# seashell.net
KiCad netlist of a schematic drawn in Altium Designer
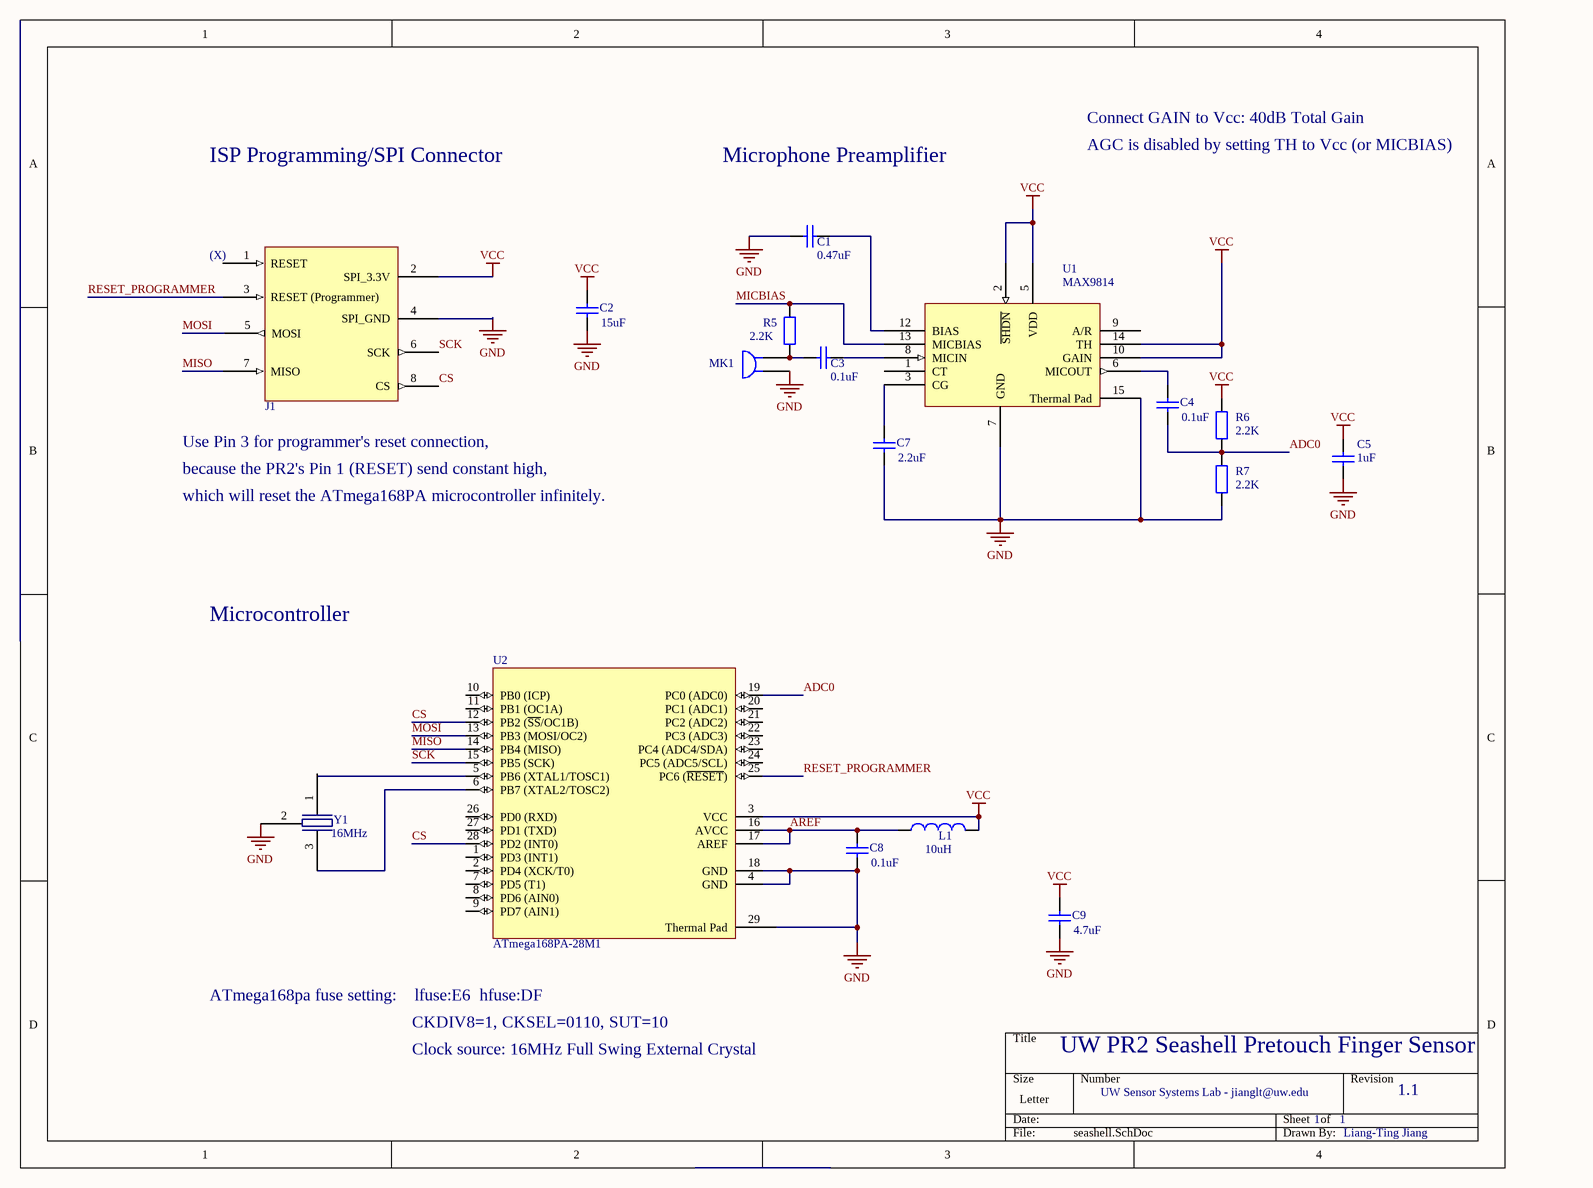
[diagram p0: seashell.SchDoc]

(export (version "E")
  (design (tool "Eeschema 10.0.6"))
  (components
    (comp (ref "C1")
      (value "0.47uF")
      (footprint "CAPC1608N")
      (description "0603 SMD Capacitor")
      (fields (field (name "PUBLISHER") "Altium Limited"))
      (libsource (lib "Miscellaneous Devices") (part "Cap"))
    )
    (comp (ref "C2")
      (value "15uF")
      (footprint "CAPC1608N")
      (description "0603 SMD Capacitor")
      (fields (field (name "PUBLISHER") "Altium Limited"))
      (libsource (lib "Miscellaneous Devices") (part "Cap"))
    )
    (comp (ref "C3")
      (value "0.1uF")
      (footprint "CAPC1608N")
      (description "0603 SMD Capacitor")
      (fields (field (name "PUBLISHER") "Altium Limited"))
      (libsource (lib "Miscellaneous Devices") (part "Cap"))
    )
    (comp (ref "C4")
      (value "0.1uF")
      (footprint "CAPC1608N")
      (description "0603 SMD Capacitor")
      (fields (field (name "PUBLISHER") "Altium Limited"))
      (libsource (lib "Miscellaneous Devices") (part "Cap"))
    )
    (comp (ref "C5")
      (value "1uF")
      (footprint "CAPC1608N")
      (description "0603 SMD Capacitor")
      (fields (field (name "PUBLISHER") "Altium Limited"))
      (libsource (lib "Miscellaneous Devices") (part "Cap"))
    )
    (comp (ref "C7")
      (value "2.2uF")
      (footprint "CAPC1608N")
      (description "0603 SMD Capacitor")
      (fields (field (name "PUBLISHER") "Altium Limited"))
      (libsource (lib "Miscellaneous Devices") (part "Cap"))
    )
    (comp (ref "C8")
      (value "0.1uF")
      (footprint "CAPC1608N")
      (description "0603 SMD Capacitor")
      (fields (field (name "PUBLISHER") "Altium Limited"))
      (libsource (lib "Miscellaneous Devices") (part "Cap"))
    )
    (comp (ref "C9")
      (value "4.7uF")
      (footprint "CAPC1608N")
      (description "0603 SMD Capacitor")
      (fields (field (name "PUBLISHER") "Altium Limited"))
      (libsource (lib "Miscellaneous Devices") (part "Cap"))
    )
    (comp (ref "J1")
      (value "FFC 8-PIN Connector (1mm)")
      (footprint "Hirose FFC connector 8-Pin")
      (description "FFC 8-PIN Connector (1mm) (SMT)")
      (libsource (lib "UW_PR2_FINERTIP_COMPONENTS") (part "FFC Connector-8Pin-SMT-1mm"))
    )
    (comp (ref "L1")
      (value "10uH")
      (footprint "INDC1608N")
      (description "0603 SMD Inductor")
      (fields (field (name "PUBLISHER") "Altium Limited"))
      (libsource (lib "Miscellaneous Devices") (part "Inductor"))
    )
    (comp (ref "MK1")
      (value "Panasonic WM-61A")
      (footprint "PIN2")
      (description "Electret Microphone")
      (fields (field (name "PUBLISHER") "Altium Limited"))
      (libsource (lib "Miscellaneous Devices") (part "Mic1"))
    )
    (comp (ref "R5")
      (value "2.2K")
      (footprint "RESC1608N")
      (description "0603 SMD Resistor")
      (fields (field (name "PUBLISHER") "Altium Limited"))
      (libsource (lib "Miscellaneous Devices") (part "Res2"))
    )
    (comp (ref "R6")
      (value "2.2K")
      (footprint "RESC1608N")
      (description "0603 SMD Resistor")
      (fields (field (name "PUBLISHER") "Altium Limited"))
      (libsource (lib "Miscellaneous Devices") (part "Res2"))
    )
    (comp (ref "R7")
      (value "2.2K")
      (footprint "RESC1608N")
      (description "0603 SMD Resistor")
      (fields (field (name "PUBLISHER") "Altium Limited"))
      (libsource (lib "Miscellaneous Devices") (part "Res2"))
    )
    (comp (ref "U1")
      (value "MAX9814")
      (footprint "QFN-14-Minnimum-Solder-Mask-Relief")
      (description "Microphone Amplifier with AGC and   Low-Noise Microphone Bias")
      (libsource (lib "UW_PR2_FINERTIP_COMPONENTS") (part "MAX9814"))
    )
    (comp (ref "U2")
      (value "ATmega168PA-28M1")
      (footprint "28M1")
      (description "8-Bit AVR Microcontroller with 8K Bytes of In-System Programmable Flash Memory")
      (fields (field (name "PUBLISHER") "Altium Limited"))
      (libsource (lib "UW_PR2_FINERTIP_COMPONENTS") (part "ATmega168-28M1"))
    )
    (comp (ref "Y1")
      (value "AVX PRQC16.00SR5010X000")
      (footprint "AVX-PRQC Ceramic Resomator SMD")
      (description "16MHz Ceramic Chip Resonator SMD")
      (fields (field (name "FREQUENCY") "16MHz"))
      (libsource (lib "UW_PR2_FINERTIP_COMPONENTS") (part "Ceramic Resonator SMT (w/ cap)"))
    )
  )
  (nets
    (net (code "1") (name "/ADC0") (class "Default")
      (node (ref "C4") (pin "1") (pinfunction "1_1") (pintype "passive"))
      (node (ref "R6") (pin "1") (pinfunction "1_1") (pintype "passive"))
      (node (ref "R7") (pin "2") (pinfunction "2_2") (pintype "passive"))
      (node (ref "U2") (pin "19") (pinfunction "PC0_(ADC0)_19") (pintype "bidirectional"))
    )
    (net (code "2") (name "/AREF") (class "Default")
      (node (ref "C8") (pin "2") (pinfunction "2_2") (pintype "passive"))
      (node (ref "L1") (pin "1") (pinfunction "1_1") (pintype "passive"))
      (node (ref "U2") (pin "16") (pinfunction "AVCC_16") (pintype "power_in"))
      (node (ref "U2") (pin "17") (pinfunction "AREF_17") (pintype "passive"))
    )
    (net (code "3") (name "/CS") (class "Default")
      (node (ref "J1") (pin "8") (pinfunction "CS_8") (pintype "output"))
      (node (ref "U2") (pin "12") (pinfunction "PB2_(~{SS}/OC1B)_12") (pintype "bidirectional"))
      (node (ref "U2") (pin "28") (pinfunction "PD2_(INT0)_28") (pintype "bidirectional"))
    )
    (net (code "4") (name "/MICBIAS") (class "Default")
      (node (ref "R5") (pin "2") (pinfunction "2_2") (pintype "passive"))
      (node (ref "U1") (pin "13") (pinfunction "MICBIAS_13") (pintype "power_in"))
    )
    (net (code "5") (name "/MISO") (class "Default")
      (node (ref "J1") (pin "7") (pinfunction "MISO_7") (pintype "input"))
      (node (ref "U2") (pin "14") (pinfunction "PB4_(MISO)_14") (pintype "bidirectional"))
    )
    (net (code "6") (name "/MOSI") (class "Default")
      (node (ref "J1") (pin "5") (pinfunction "MOSI_5") (pintype "output"))
      (node (ref "U2") (pin "13") (pinfunction "PB3_(MOSI/OC2)_13") (pintype "bidirectional"))
    )
    (net (code "7") (name "/RESET_PROGRAMMER") (class "Default")
      (node (ref "J1") (pin "3") (pinfunction "RESET_(Programmer)_3") (pintype "input"))
      (node (ref "U2") (pin "25") (pinfunction "PC6_(~{RESET})_25") (pintype "bidirectional"))
    )
    (net (code "8") (name "/SCK") (class "Default")
      (node (ref "J1") (pin "6") (pinfunction "SCK_6") (pintype "output"))
      (node (ref "U2") (pin "15") (pinfunction "PB5_(SCK)_15") (pintype "bidirectional"))
    )
    (net (code "9") (name "GND") (class "Default")
      (node (ref "C1") (pin "2") (pinfunction "2_2") (pintype "passive"))
      (node (ref "C2") (pin "2") (pinfunction "2_2") (pintype "passive"))
      (node (ref "C5") (pin "1") (pinfunction "1_1") (pintype "passive"))
      (node (ref "C7") (pin "2") (pinfunction "2_2") (pintype "passive"))
      (node (ref "C8") (pin "1") (pinfunction "1_1") (pintype "passive"))
      (node (ref "C9") (pin "2") (pinfunction "2_2") (pintype "passive"))
      (node (ref "J1") (pin "4") (pinfunction "SPI_GND_4") (pintype "power_in"))
      (node (ref "MK1") (pin "1") (pinfunction "1_1") (pintype "passive"))
      (node (ref "R7") (pin "1") (pinfunction "1_1") (pintype "passive"))
      (node (ref "U1") (pin "15") (pinfunction "Thermal_Pad_15") (pintype "passive"))
      (node (ref "U1") (pin "7") (pinfunction "GND_7") (pintype "power_in"))
      (node (ref "U2") (pin "18") (pinfunction "GND_18") (pintype "power_in"))
      (node (ref "U2") (pin "29") (pinfunction "Thermal_Pad_29") (pintype "power_in"))
      (node (ref "U2") (pin "4") (pinfunction "GND_4") (pintype "power_in"))
      (node (ref "Y1") (pin "2") (pinfunction "GND_2") (pintype "power_in"))
    )
    (net (code "10") (name "Net-(C3-Pad1)") (class "Default")
      (node (ref "C3") (pin "1") (pinfunction "1_1") (pintype "passive"))
      (node (ref "MK1") (pin "2") (pinfunction "2_2") (pintype "passive"))
      (node (ref "R5") (pin "1") (pinfunction "1_1") (pintype "passive"))
    )
    (net (code "11") (name "Net-(U1-BIAS)") (class "Default")
      (node (ref "C1") (pin "1") (pinfunction "1_1") (pintype "passive"))
      (node (ref "U1") (pin "12") (pinfunction "BIAS_12") (pintype "passive"))
    )
    (net (code "12") (name "Net-(U1-CG)") (class "Default")
      (node (ref "C7") (pin "1") (pinfunction "1_1") (pintype "passive"))
      (node (ref "U1") (pin "3") (pinfunction "CG_3") (pintype "passive"))
    )
    (net (code "13") (name "Net-(U1-MICIN)") (class "Default")
      (node (ref "C3") (pin "2") (pinfunction "2_2") (pintype "passive"))
      (node (ref "U1") (pin "8") (pinfunction "MICIN_8") (pintype "input"))
    )
    (net (code "14") (name "Net-(U1-MICOUT)") (class "Default")
      (node (ref "C4") (pin "2") (pinfunction "2_2") (pintype "passive"))
      (node (ref "U1") (pin "6") (pinfunction "MICOUT_6") (pintype "output"))
    )
    (net (code "15") (name "Net-(U2-PB6_(XTAL1{slash}TOSC1))") (class "Default")
      (node (ref "U2") (pin "5") (pinfunction "PB6_(XTAL1/TOSC1)_5") (pintype "bidirectional"))
      (node (ref "Y1") (pin "1") (pinfunction "IN/OUT_1") (pintype "passive"))
    )
    (net (code "16") (name "Net-(U2-PB7_(XTAL2{slash}TOSC2))") (class "Default")
      (node (ref "U2") (pin "6") (pinfunction "PB7_(XTAL2/TOSC2)_6") (pintype "bidirectional"))
      (node (ref "Y1") (pin "3") (pinfunction "OUT/IN_3") (pintype "passive"))
    )
    (net (code "17") (name "VCC") (class "Default")
      (node (ref "C2") (pin "1") (pinfunction "1_1") (pintype "passive"))
      (node (ref "C5") (pin "2") (pinfunction "2_2") (pintype "passive"))
      (node (ref "C9") (pin "1") (pinfunction "1_1") (pintype "passive"))
      (node (ref "J1") (pin "2") (pinfunction "SPI_3.3V_2") (pintype "power_in"))
      (node (ref "L1") (pin "2") (pinfunction "2_2") (pintype "passive"))
      (node (ref "R6") (pin "2") (pinfunction "2_2") (pintype "passive"))
      (node (ref "U1") (pin "10") (pinfunction "GAIN_10") (pintype "passive"))
      (node (ref "U1") (pin "14") (pinfunction "TH_14") (pintype "passive"))
      (node (ref "U1") (pin "2") (pinfunction "~{SHDN}_2") (pintype "input"))
      (node (ref "U1") (pin "5") (pinfunction "VDD_5") (pintype "power_in"))
      (node (ref "U2") (pin "3") (pinfunction "VCC_3") (pintype "power_in"))
    )
    (net (code "18") (name "unconnected-(J1-RESET-Pad1)") (class "Default")
      (node (ref "J1") (pin "1") (pinfunction "RESET_1") (pintype "input"))
    )
    (net (code "19") (name "unconnected-(U1-A{slash}R-Pad9)") (class "Default")
      (node (ref "U1") (pin "9") (pinfunction "A/R_9") (pintype "passive"))
    )
    (net (code "20") (name "unconnected-(U1-CT-Pad1)") (class "Default")
      (node (ref "U1") (pin "1") (pinfunction "CT_1") (pintype "passive"))
    )
    (net (code "21") (name "unconnected-(U1-NC-Pad4)") (class "Default")
      (node (ref "U1") (pin "4") (pinfunction "NC_4") (pintype "passive"))
    )
    (net (code "22") (name "unconnected-(U1-NC-Pad11)") (class "Default")
      (node (ref "U1") (pin "11") (pinfunction "NC_11") (pintype "passive"))
    )
    (net (code "23") (name "unconnected-(U2-PB0_(ICP)-Pad10)") (class "Default")
      (node (ref "U2") (pin "10") (pinfunction "PB0_(ICP)_10") (pintype "bidirectional"))
    )
    (net (code "24") (name "unconnected-(U2-PB1_(OC1A)-Pad11)") (class "Default")
      (node (ref "U2") (pin "11") (pinfunction "PB1_(OC1A)_11") (pintype "bidirectional"))
    )
    (net (code "25") (name "unconnected-(U2-PC1_(ADC1)-Pad20)") (class "Default")
      (node (ref "U2") (pin "20") (pinfunction "PC1_(ADC1)_20") (pintype "bidirectional"))
    )
    (net (code "26") (name "unconnected-(U2-PC2_(ADC2)-Pad21)") (class "Default")
      (node (ref "U2") (pin "21") (pinfunction "PC2_(ADC2)_21") (pintype "bidirectional"))
    )
    (net (code "27") (name "unconnected-(U2-PC3_(ADC3)-Pad22)") (class "Default")
      (node (ref "U2") (pin "22") (pinfunction "PC3_(ADC3)_22") (pintype "bidirectional"))
    )
    (net (code "28") (name "unconnected-(U2-PC4_(ADC4{slash}SDA)-Pad23)") (class "Default")
      (node (ref "U2") (pin "23") (pinfunction "PC4_(ADC4/SDA)_23") (pintype "bidirectional"))
    )
    (net (code "29") (name "unconnected-(U2-PC5_(ADC5{slash}SCL)-Pad24)") (class "Default")
      (node (ref "U2") (pin "24") (pinfunction "PC5_(ADC5/SCL)_24") (pintype "bidirectional"))
    )
    (net (code "30") (name "unconnected-(U2-PD0_(RXD)-Pad26)") (class "Default")
      (node (ref "U2") (pin "26") (pinfunction "PD0_(RXD)_26") (pintype "bidirectional"))
    )
    (net (code "31") (name "unconnected-(U2-PD1_(TXD)-Pad27)") (class "Default")
      (node (ref "U2") (pin "27") (pinfunction "PD1_(TXD)_27") (pintype "bidirectional"))
    )
    (net (code "32") (name "unconnected-(U2-PD3_(INT1)-Pad1)") (class "Default")
      (node (ref "U2") (pin "1") (pinfunction "PD3_(INT1)_1") (pintype "bidirectional"))
    )
    (net (code "33") (name "unconnected-(U2-PD4_(XCK{slash}T0)-Pad2)") (class "Default")
      (node (ref "U2") (pin "2") (pinfunction "PD4_(XCK/T0)_2") (pintype "bidirectional"))
    )
    (net (code "34") (name "unconnected-(U2-PD5_(T1)-Pad7)") (class "Default")
      (node (ref "U2") (pin "7") (pinfunction "PD5_(T1)_7") (pintype "bidirectional"))
    )
    (net (code "35") (name "unconnected-(U2-PD6_(AIN0)-Pad8)") (class "Default")
      (node (ref "U2") (pin "8") (pinfunction "PD6_(AIN0)_8") (pintype "bidirectional"))
    )
    (net (code "36") (name "unconnected-(U2-PD7_(AIN1)-Pad9)") (class "Default")
      (node (ref "U2") (pin "9") (pinfunction "PD7_(AIN1)_9") (pintype "bidirectional"))
    )
  )
)
